# LowPass.net
KiCad netlist of a schematic drawn in EAGLE
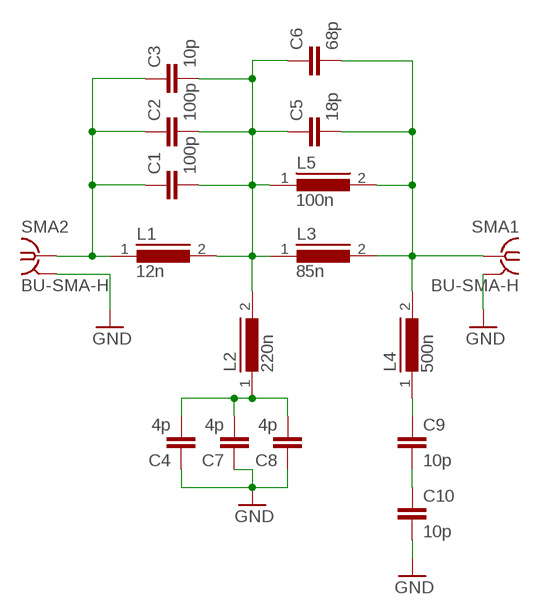
[diagram p0: schematic, sheet 1]

(export (version "E")
  (design (tool "Eeschema 10.0.6"))
  (components
    (comp (ref "C1")
      (value "100p")
      (footprint "eagle-import:C0805")
      (libsource (lib "eagle-import") (part "C-EUC0805"))
    )
    (comp (ref "C2")
      (value "100p")
      (footprint "eagle-import:C0805")
      (libsource (lib "eagle-import") (part "C-EUC0805"))
    )
    (comp (ref "C3")
      (value "10p")
      (footprint "eagle-import:C0805")
      (libsource (lib "eagle-import") (part "C-EUC0805"))
    )
    (comp (ref "C4")
      (value "4p")
      (footprint "eagle-import:C1206")
      (libsource (lib "eagle-import") (part "C-EUC1206"))
    )
    (comp (ref "C5")
      (value "18p")
      (footprint "eagle-import:C0805")
      (libsource (lib "eagle-import") (part "C-EUC0805"))
    )
    (comp (ref "C6")
      (value "68p")
      (footprint "eagle-import:C0402")
      (libsource (lib "eagle-import") (part "C-EUC0402"))
    )
    (comp (ref "C7")
      (value "4p")
      (footprint "eagle-import:C1206")
      (libsource (lib "eagle-import") (part "C-EUC1206"))
    )
    (comp (ref "C8")
      (value "4p")
      (footprint "eagle-import:C1206")
      (libsource (lib "eagle-import") (part "C-EUC1206"))
    )
    (comp (ref "C9")
      (value "10p")
      (footprint "eagle-import:C0805")
      (libsource (lib "eagle-import") (part "C-EUC0805"))
    )
    (comp (ref "C10")
      (value "10p")
      (footprint "eagle-import:C0805")
      (libsource (lib "eagle-import") (part "C-EUC0805"))
    )
    (comp (ref "L1")
      (value "12n")
      (footprint "eagle-import:MICC10")
      (libsource (lib "eagle-import") (part "MICC10"))
    )
    (comp (ref "L2")
      (value "220n")
      (footprint "eagle-import:MICC10")
      (libsource (lib "eagle-import") (part "MICC10"))
    )
    (comp (ref "L3")
      (value "85n")
      (footprint "eagle-import:MICC10")
      (libsource (lib "eagle-import") (part "MICC10"))
    )
    (comp (ref "L4")
      (value "500n")
      (footprint "eagle-import:MICC10")
      (libsource (lib "eagle-import") (part "MICC10"))
    )
    (comp (ref "L5")
      (value "100n")
      (footprint "eagle-import:MICC10")
      (libsource (lib "eagle-import") (part "MICC10"))
    )
    (comp (ref "SMA1")
      (value "BU-SMA-H")
      (footprint "eagle-import:BU-SMA-H")
      (libsource (lib "eagle-import") (part "BU-SMA-H"))
    )
    (comp (ref "SMA2")
      (value "BU-SMA-H")
      (footprint "eagle-import:BU-SMA-H")
      (libsource (lib "eagle-import") (part "BU-SMA-H"))
    )
  )
  (nets
    (net (code "1") (name "GND") (class "Default")
      (node (ref "C10") (pin "2") (pinfunction "2_2") (pintype "passive"))
      (node (ref "C4") (pin "1") (pinfunction "1_1") (pintype "passive"))
      (node (ref "C7") (pin "1") (pinfunction "1_1") (pintype "passive"))
      (node (ref "C8") (pin "1") (pinfunction "1_1") (pintype "passive"))
      (node (ref "SMA1") (pin "2") (pinfunction "2_2") (pintype "passive"))
      (node (ref "SMA1") (pin "3") (pinfunction "2_3") (pintype "passive"))
      (node (ref "SMA1") (pin "4") (pinfunction "2_4") (pintype "passive"))
      (node (ref "SMA1") (pin "5") (pinfunction "2_5") (pintype "passive"))
      (node (ref "SMA2") (pin "2") (pinfunction "2_2") (pintype "passive"))
      (node (ref "SMA2") (pin "3") (pinfunction "2_3") (pintype "passive"))
      (node (ref "SMA2") (pin "4") (pinfunction "2_4") (pintype "passive"))
      (node (ref "SMA2") (pin "5") (pinfunction "2_5") (pintype "passive"))
    )
    (net (code "2") (name "Net-(C1-Pad1)") (class "Default")
      (node (ref "C1") (pin "1") (pinfunction "1_1") (pintype "passive"))
      (node (ref "C2") (pin "1") (pinfunction "1_1") (pintype "passive"))
      (node (ref "C3") (pin "1") (pinfunction "1_1") (pintype "passive"))
      (node (ref "L1") (pin "1") (pinfunction "1_1") (pintype "passive"))
      (node (ref "SMA2") (pin "1") (pinfunction "1_1") (pintype "passive"))
    )
    (net (code "3") (name "Net-(C1-Pad2)") (class "Default")
      (node (ref "C1") (pin "2") (pinfunction "2_2") (pintype "passive"))
      (node (ref "C2") (pin "2") (pinfunction "2_2") (pintype "passive"))
      (node (ref "C3") (pin "2") (pinfunction "2_2") (pintype "passive"))
      (node (ref "C5") (pin "1") (pinfunction "1_1") (pintype "passive"))
      (node (ref "C6") (pin "1") (pinfunction "1_1") (pintype "passive"))
      (node (ref "L1") (pin "2") (pinfunction "2_2") (pintype "passive"))
      (node (ref "L2") (pin "2") (pinfunction "2_2") (pintype "passive"))
      (node (ref "L3") (pin "1") (pinfunction "1_1") (pintype "passive"))
      (node (ref "L5") (pin "1") (pinfunction "1_1") (pintype "passive"))
    )
    (net (code "4") (name "Net-(C4-Pad2)") (class "Default")
      (node (ref "C4") (pin "2") (pinfunction "2_2") (pintype "passive"))
      (node (ref "C7") (pin "2") (pinfunction "2_2") (pintype "passive"))
      (node (ref "C8") (pin "2") (pinfunction "2_2") (pintype "passive"))
      (node (ref "L2") (pin "1") (pinfunction "1_1") (pintype "passive"))
    )
    (net (code "5") (name "Net-(C5-Pad2)") (class "Default")
      (node (ref "C5") (pin "2") (pinfunction "2_2") (pintype "passive"))
      (node (ref "C6") (pin "2") (pinfunction "2_2") (pintype "passive"))
      (node (ref "L3") (pin "2") (pinfunction "2_2") (pintype "passive"))
      (node (ref "L4") (pin "2") (pinfunction "2_2") (pintype "passive"))
      (node (ref "L5") (pin "2") (pinfunction "2_2") (pintype "passive"))
      (node (ref "SMA1") (pin "1") (pinfunction "1_1") (pintype "passive"))
    )
    (net (code "6") (name "Net-(C9-Pad1)") (class "Default")
      (node (ref "C9") (pin "1") (pinfunction "1_1") (pintype "passive"))
      (node (ref "L4") (pin "1") (pinfunction "1_1") (pintype "passive"))
    )
    (net (code "7") (name "Net-(C10-Pad1)") (class "Default")
      (node (ref "C10") (pin "1") (pinfunction "1_1") (pintype "passive"))
      (node (ref "C9") (pin "2") (pinfunction "2_2") (pintype "passive"))
    )
  )
)
